# LED_strip.net
KiCad netlist of a schematic drawn in Altium Designer
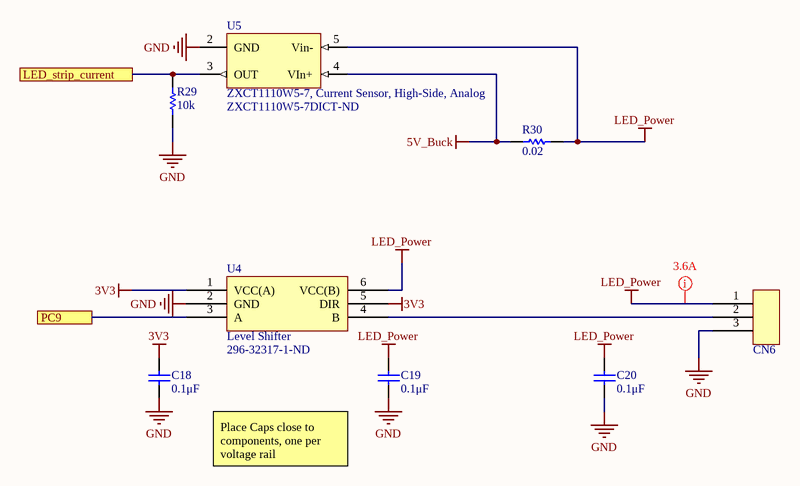
[diagram p0: LED strip.SchDoc]

(export (version "E")
  (design (tool "Eeschema 10.0.6"))
  (components
    (comp (ref "C18")
      (value "0.1μF")
      (footprint "CAPC1608N(0603\")")
      (description "Capacitor, Ceramic, 16V, +/- 10%, 0603 SMD, X7R")
      (fields (field (name "PUBLISHER") "AUVic") (field (name "CREATED BY") "Andy Bates"))
      (libsource (lib "AUVic_Integrated_Library_Capacitors") (part "0.1uF 16V 0603 SMD, Ceramic"))
    )
    (comp (ref "C19")
      (value "0.1μF")
      (footprint "CAPC1608N(0603\")")
      (description "Capacitor, Ceramic, 16V, +/- 10%, 0603 SMD, X7R")
      (fields (field (name "PUBLISHER") "AUVic") (field (name "CREATED BY") "Andy Bates"))
      (libsource (lib "AUVic_Integrated_Library_Capacitors") (part "0.1uF 16V 0603 SMD, Ceramic"))
    )
    (comp (ref "C20")
      (value "0.1μF")
      (footprint "CAPC1608N(0603\")")
      (description "Capacitor, Ceramic, 16V, +/- 10%, 0603 SMD, X7R")
      (fields (field (name "PUBLISHER") "AUVic") (field (name "CREATED BY") "Andy Bates"))
      (libsource (lib "AUVic_Integrated_Library_Capacitors") (part "0.1uF 16V 0603 SMD, Ceramic"))
    )
    (comp (ref "CN6")
      (value "B3PS-VH(LF)(SN)")
      (footprint "3X1 Male Header, Locking, 10A")
      (description "CONN HEADER VH SIDE 3POS 3.96MM")
      (fields (field (name "MADE BY") "Robert Keen"))
      (libsource (lib "AUVic_Integrated_Library_Connectors") (part "3x1 Male Header, Locking, 10A"))
    )
    (comp (ref "R29")
      (value "10k")
      (footprint "RESC1608N(0603\")")
      (description "10kR, 1%, 1/10W, 0603 SMD")
      (fields (field (name "MADE BY") "Ashwin Sira"))
      (libsource (lib "AUVic_Integrated_Library_Resistors") (part "10kR, 1%, 1/10W, 0603 SMD"))
    )
    (comp (ref "R30")
      (value "0.02")
      (footprint "RESC6332N(2512\")")
      (description "0R02, 1%, 2W, 2512 SMD")
      (fields (field (name "CREATED BY") "Robert Keen"))
      (libsource (lib "AUVic_Integrated_Library_Resistors") (part "0R02, 1%, 2W, 2512 SMD"))
    )
    (comp (ref "U4")
      (value "Level Shifter")
      (footprint "SOT-363")
      (description "Voltage Level Translator Bidirectional 1 Circuit 1 Channel 420Mbps SC-88 (SOT-363)")
      (fields (field (name "SUPPLIER PART NUMBER 1") "296-32317-1-ND") (field (name "MADE BY") "Andy Bates"))
      (libsource (lib "AUVic_Integrated_Library_Logic") (part "Bidirectional Level Shifter, 1.65V - 5.5V VCCA, 1.65V - 5.5V VCCB"))
    )
    (comp (ref "U5")
      (value "ZXCT1110W5-7, Current Sensor, High-Side, Analog")
      (footprint "SOT23-5")
      (description "Diodes Incorporated, ZXCT1110W5-7")
      (fields
        (field (name "SUPPLIER PART NUMBER 1") "ZXCT1110W5-7DICT-ND")
        (field (name "CREATED BY") "Jacob Lower")
        (field (name "PUBLISHER") "AUVic")
      )
      (libsource (lib "AUVic_Schematic_Library_Sensors") (part "ZXCT1110W5-7, Current Sensor, High-Side, Analog"))
    )
  )
  (nets
    (net (code "1") (name "/LED_strip_current") (class "Default")
      (node (ref "R29") (pin "2") (pinfunction "2_2") (pintype "passive"))
      (node (ref "U5") (pin "3") (pinfunction "OUT_3") (pintype "output"))
    )
    (net (code "2") (name "/PC9") (class "Default")
      (node (ref "U4") (pin "3") (pinfunction "A_3") (pintype "passive"))
    )
    (net (code "3") (name "3V3") (class "Default")
      (node (ref "C18") (pin "1") (pinfunction "Anode_1") (pintype "passive"))
      (node (ref "U4") (pin "1") (pinfunction "VCC(A)_1") (pintype "passive"))
      (node (ref "U4") (pin "5") (pinfunction "DIR_5") (pintype "passive"))
    )
    (net (code "4") (name "5V_Buck") (class "Default")
      (node (ref "R30") (pin "1") (pinfunction "1_1") (pintype "passive"))
      (node (ref "U5") (pin "4") (pinfunction "VIn+_4") (pintype "input"))
    )
    (net (code "5") (name "GND") (class "Default")
      (node (ref "C18") (pin "2") (pinfunction "Cathode_2") (pintype "passive"))
      (node (ref "C19") (pin "2") (pinfunction "Cathode_2") (pintype "passive"))
      (node (ref "C20") (pin "2") (pinfunction "Cathode_2") (pintype "passive"))
      (node (ref "CN6") (pin "3") (pintype "passive"))
      (node (ref "R29") (pin "1") (pinfunction "1_1") (pintype "passive"))
      (node (ref "U4") (pin "2") (pinfunction "GND_2") (pintype "passive"))
      (node (ref "U5") (pin "2") (pinfunction "GND_2") (pintype "power_in"))
    )
    (net (code "6") (name "LED_Power") (class "Default")
      (node (ref "C19") (pin "1") (pinfunction "Anode_1") (pintype "passive"))
      (node (ref "C20") (pin "1") (pinfunction "Anode_1") (pintype "passive"))
      (node (ref "CN6") (pin "1") (pintype "passive"))
      (node (ref "R30") (pin "2") (pinfunction "2_2") (pintype "passive"))
      (node (ref "U4") (pin "6") (pinfunction "VCC(B)_6") (pintype "passive"))
      (node (ref "U5") (pin "5") (pinfunction "Vin-_5") (pintype "input"))
    )
    (net (code "7") (name "Net-(U4-B)") (class "Default")
      (node (ref "CN6") (pin "2") (pintype "passive"))
      (node (ref "U4") (pin "4") (pinfunction "B_4") (pintype "passive"))
    )
  )
)
